# ArbPwrBoost_P2.net
KiCad netlist of a schematic drawn in Altium Designer
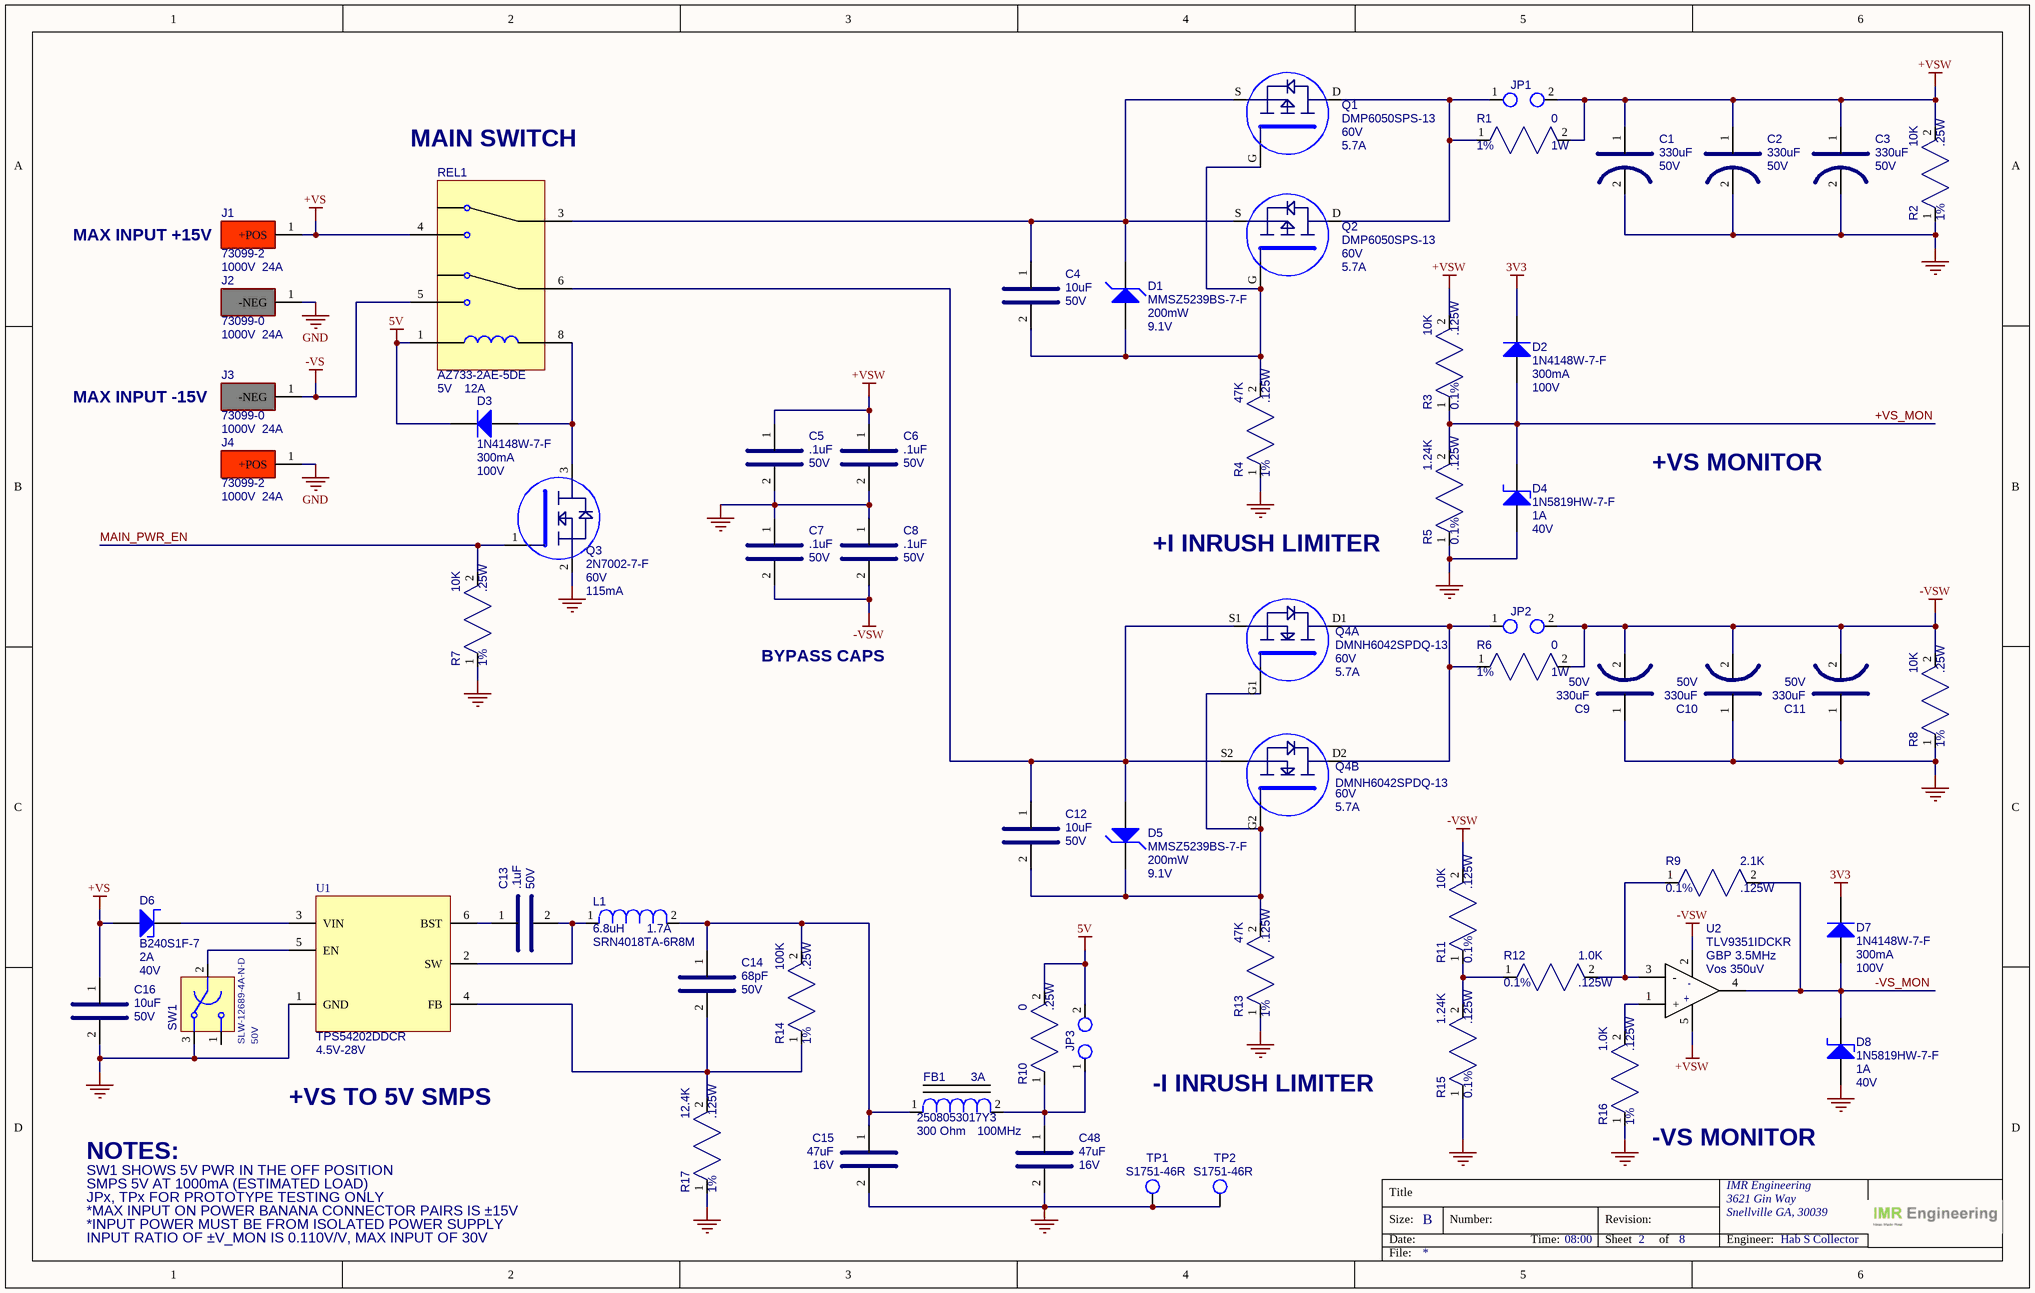
[diagram p0: ArbPwrBoost_P2.SchDoc]

(export (version "E")
  (design (tool "Eeschema 10.0.6"))
  (components
    (comp (ref "C1")
      (value "330uF")
      (footprint "PANASONIC_EEEFK0J332AQ")
      (description "CAP ALE 330UF 20% 50V SMD")
      (fields
        (field (name "MFG") "EEV-FK1H331Q")
        (field (name "VOLTAGE") "50V")
        (field (name "Comment") "Panasonic Electronic")
      )
      (libsource (lib "IMR_LIB_SCH_R2") (part "CAP_330UF_50V_ALE"))
    )
    (comp (ref "C2")
      (value "330uF")
      (footprint "PANASONIC_EEEFK0J332AQ")
      (description "CAP ALE 330UF 20% 50V SMD")
      (fields
        (field (name "MFG") "EEV-FK1H331Q")
        (field (name "VOLTAGE") "50V")
        (field (name "Comment") "Panasonic Electronic")
      )
      (libsource (lib "IMR_LIB_SCH_R2") (part "CAP_330UF_50V_ALE"))
    )
    (comp (ref "C3")
      (value "330uF")
      (footprint "PANASONIC_EEEFK0J332AQ")
      (description "CAP ALE 330UF 20% 50V SMD")
      (fields
        (field (name "MFG") "EEV-FK1H331Q")
        (field (name "VOLTAGE") "50V")
        (field (name "Comment") "Panasonic Electronic")
      )
      (libsource (lib "IMR_LIB_SCH_R2") (part "CAP_330UF_50V_ALE"))
    )
    (comp (ref "C4")
      (value "10uF")
      (footprint "CAP_0805")
      (description "CAP CER 10UF 50V X5R 0805")
      (fields
        (field (name "MFG") "Murata Electronics")
        (field (name "VOLTAGE") "50V")
        (field (name "Comment") "GRM21BR61H106KE43L")
      )
      (libsource (lib "IMR_LIB_SCH_R2") (part "CAP_SMD_10UF_50V_0805"))
    )
    (comp (ref "C5")
      (value ".1uF")
      (footprint "CAP_0805")
      (description "CAP CER 0.1UF 50V X7R 0805")
      (fields
        (field (name "MFG") "KYOCERA AVX")
        (field (name "VOLTAGE") "50V")
        (field (name "Comment") "KGM21NR71H104KT")
      )
      (libsource (lib "IMR_LIB_SCH_R2") (part "CAP_SMD_0.1UF_50V_0805"))
    )
    (comp (ref "C6")
      (value ".1uF")
      (footprint "CAP_0805")
      (description "CAP CER 0.1UF 50V X7R 0805")
      (fields
        (field (name "MFG") "KYOCERA AVX")
        (field (name "VOLTAGE") "50V")
        (field (name "Comment") "KGM21NR71H104KT")
      )
      (libsource (lib "IMR_LIB_SCH_R2") (part "CAP_SMD_0.1UF_50V_0805"))
    )
    (comp (ref "C7")
      (value ".1uF")
      (footprint "CAP_0805")
      (description "CAP CER 0.1UF 50V X7R 0805")
      (fields
        (field (name "MFG") "KYOCERA AVX")
        (field (name "VOLTAGE") "50V")
        (field (name "Comment") "KGM21NR71H104KT")
      )
      (libsource (lib "IMR_LIB_SCH_R2") (part "CAP_SMD_0.1UF_50V_0805"))
    )
    (comp (ref "C8")
      (value ".1uF")
      (footprint "CAP_0805")
      (description "CAP CER 0.1UF 50V X7R 0805")
      (fields
        (field (name "MFG") "KYOCERA AVX")
        (field (name "VOLTAGE") "50V")
        (field (name "Comment") "KGM21NR71H104KT")
      )
      (libsource (lib "IMR_LIB_SCH_R2") (part "CAP_SMD_0.1UF_50V_0805"))
    )
    (comp (ref "C9")
      (value "330uF")
      (footprint "PANASONIC_EEEFK0J332AQ")
      (description "CAP ALE 330UF 20% 50V SMD")
      (fields
        (field (name "MFG") "EEV-FK1H331Q")
        (field (name "VOLTAGE") "50V")
        (field (name "Comment") "Panasonic Electronic")
      )
      (libsource (lib "IMR_LIB_SCH_R2") (part "CAP_330UF_50V_ALE"))
    )
    (comp (ref "C10")
      (value "330uF")
      (footprint "PANASONIC_EEEFK0J332AQ")
      (description "CAP ALE 330UF 20% 50V SMD")
      (fields
        (field (name "MFG") "EEV-FK1H331Q")
        (field (name "VOLTAGE") "50V")
        (field (name "Comment") "Panasonic Electronic")
      )
      (libsource (lib "IMR_LIB_SCH_R2") (part "CAP_330UF_50V_ALE"))
    )
    (comp (ref "C11")
      (value "330uF")
      (footprint "PANASONIC_EEEFK0J332AQ")
      (description "CAP ALE 330UF 20% 50V SMD")
      (fields
        (field (name "MFG") "EEV-FK1H331Q")
        (field (name "VOLTAGE") "50V")
        (field (name "Comment") "Panasonic Electronic")
      )
      (libsource (lib "IMR_LIB_SCH_R2") (part "CAP_330UF_50V_ALE"))
    )
    (comp (ref "C12")
      (value "10uF")
      (footprint "CAP_0805")
      (description "CAP CER 10UF 50V X5R 0805")
      (fields
        (field (name "MFG") "Murata Electronics")
        (field (name "VOLTAGE") "50V")
        (field (name "Comment") "GRM21BR61H106KE43L")
      )
      (libsource (lib "IMR_LIB_SCH_R2") (part "CAP_SMD_10UF_50V_0805"))
    )
    (comp (ref "C13")
      (value ".1uF")
      (footprint "CAP_0805")
      (description "CAP CER 0.1UF 50V X7R 0805")
      (fields
        (field (name "MFG") "KYOCERA AVX")
        (field (name "VOLTAGE") "50V")
        (field (name "Comment") "KGM21NR71H104KT")
      )
      (libsource (lib "IMR_LIB_SCH_R2") (part "CAP_SMD_0.1UF_50V_0805"))
    )
    (comp (ref "C14")
      (value "68pF")
      (footprint "CAP_0805")
      (description "CAP CER 68PF 50V X7R 0805")
      (fields
        (field (name "MFG") "KEMET")
        (field (name "VOLTAGE") "50V")
        (field (name "Comment") "C0805C680K5RACAUTO")
      )
      (libsource (lib "IMR_LIB_SCH_R2") (part "CAP_SMD_68PF_50V_0805"))
    )
    (comp (ref "C15")
      (value "47uF")
      (footprint "CAP_1210")
      (description "CAP CER 47UF 50V X5R 1210")
      (fields
        (field (name "MFG") "Murata Electronics")
        (field (name "VOLTAGE") "16V")
        (field (name "Comment") "GRM32ER60J476ME20L")
      )
      (libsource (lib "IMR_LIB_SCH_R2") (part "CAP_SMD_47UF_16V_1210"))
    )
    (comp (ref "C16")
      (value "10uF")
      (footprint "CAP_0805")
      (description "CAP CER 10UF 50V X5R 0805")
      (fields
        (field (name "MFG") "Murata Electronics")
        (field (name "VOLTAGE") "50V")
        (field (name "Comment") "GRM21BR61H106KE43L")
      )
      (libsource (lib "IMR_LIB_SCH_R2") (part "CAP_SMD_10UF_50V_0805"))
    )
    (comp (ref "C48")
      (value "47uF")
      (footprint "CAP_1210")
      (description "CAP CER 47UF 50V X5R 1210")
      (fields
        (field (name "MFG") "Murata Electronics")
        (field (name "VOLTAGE") "16V")
        (field (name "Comment") "GRM32ER60J476ME20L")
      )
      (libsource (lib "IMR_LIB_SCH_R2") (part "CAP_SMD_47UF_16V_1210"))
    )
    (comp (ref "D1")
      (value "9.1V")
      (footprint "SOD323")
      (description "DIODE ZENER 9.1V 200MW SOD323")
      (fields
        (field (name "MFG") "Diodes Inc")
        (field (name "MFG_PN") "MMSZ5239BS-7-F")
        (field (name "POWER") "200mW")
        (field (name "Comment") "MMSZ5239BS-7-F")
      )
      (libsource (lib "IMR_LIB_SCH_R2") (part "DIODE_ZENER_MMSZ5239BS-7-F"))
    )
    (comp (ref "D2")
      (value "100V")
      (footprint "SOD123")
      (description "RELAY REED SPDT 250MA 5V")
      (fields
        (field (name "MFG") "Diodes Inc")
        (field (name "MFG_PN") "1N4148W-7-F")
        (field (name "CURRENT") "300mA")
        (field (name "Comment") "1N4148W-7-F")
      )
      (libsource (lib "IMR_LIB_SCH_R2") (part "DIODE_1N4148W-7-F"))
    )
    (comp (ref "D3")
      (value "100V")
      (footprint "SOD123")
      (description "RELAY REED SPDT 250MA 5V")
      (fields
        (field (name "MFG") "Diodes Inc")
        (field (name "MFG_PN") "1N4148W-7-F")
        (field (name "CURRENT") "300mA")
        (field (name "Comment") "1N4148W-7-F")
      )
      (libsource (lib "IMR_LIB_SCH_R2") (part "DIODE_1N4148W-7-F"))
    )
    (comp (ref "D4")
      (value "40V")
      (footprint "SOD123")
      (description "DIODE SCHOTTKY 40V 1A SOD123")
      (fields
        (field (name "MFG") "Diodes Inc")
        (field (name "MFG_PN") "1N5819HW-7-F")
        (field (name "CURRENT") "1A")
        (field (name "Comment") "1N5819HW-7-F")
      )
      (libsource (lib "IMR_LIB_SCH_R2") (part "DIODE_SCHOTTKY_1N5819HW-7-F"))
    )
    (comp (ref "D5")
      (value "9.1V")
      (footprint "SOD323")
      (description "DIODE ZENER 9.1V 200MW SOD323")
      (fields
        (field (name "MFG") "Diodes Inc")
        (field (name "MFG_PN") "MMSZ5239BS-7-F")
        (field (name "POWER") "200mW")
        (field (name "Comment") "MMSZ5239BS-7-F")
      )
      (libsource (lib "IMR_LIB_SCH_R2") (part "DIODE_ZENER_MMSZ5239BS-7-F"))
    )
    (comp (ref "D6")
      (value "40V")
      (footprint "SOD123F")
      (description "DIODE SCHOTTKY 40V 2A SOD123F")
      (fields
        (field (name "MFG") "Diodes Inc")
        (field (name "MFG_PN") "B240S1F-7")
        (field (name "CURRENT") "2A")
        (field (name "Comment") "B240S1F-7")
      )
      (libsource (lib "IMR_LIB_SCH_R2") (part "DIODE_SCHOTTKY_B240S1F-7"))
    )
    (comp (ref "D7")
      (value "100V")
      (footprint "SOD123")
      (description "RELAY REED SPDT 250MA 5V")
      (fields
        (field (name "MFG") "Diodes Inc")
        (field (name "MFG_PN") "1N4148W-7-F")
        (field (name "CURRENT") "300mA")
        (field (name "Comment") "1N4148W-7-F")
      )
      (libsource (lib "IMR_LIB_SCH_R2") (part "DIODE_1N4148W-7-F"))
    )
    (comp (ref "D8")
      (value "40V")
      (footprint "SOD123")
      (description "DIODE SCHOTTKY 40V 1A SOD123")
      (fields
        (field (name "MFG") "Diodes Inc")
        (field (name "MFG_PN") "1N5819HW-7-F")
        (field (name "CURRENT") "1A")
        (field (name "Comment") "1N5819HW-7-F")
      )
      (libsource (lib "IMR_LIB_SCH_R2") (part "DIODE_SCHOTTKY_1N5819HW-7-F"))
    )
    (comp (ref "FB1")
      (value "300 Ohm")
      (footprint "FERRITE_0805")
      (description "FERRITE BEAD 300 OHM 0805 1LN")
      (fields
        (field (name "MFG") "Fair-Rite")
        (field (name "FREQUENCY") "100MHz")
        (field (name "MFG_PN") "2508053017Y3")
        (field (name "CURRENT") "3A")
        (field (name "Comment") "2508053017Y3")
      )
      (libsource (lib "IMR_LIB_SCH_R2") (part "FERRITE_2508053017Y3"))
    )
    (comp (ref "J1")
      (value "1000V")
      (footprint "Pomona_73099-2")
      (description "CONN 4mm Banana Socket Right Angle PCB RED")
      (fields
        (field (name "MFG") "Pomona")
        (field (name "MFG_PN") "73099-2")
        (field (name "CURRENT") "24A")
        (field (name "Comment") "73099-2")
      )
      (libsource (lib "IMR_LIB_SCH_R2") (part "CONN_PANOMA_73099-2"))
    )
    (comp (ref "J2")
      (value "1000V")
      (footprint "Pomona_73099-0")
      (description "CONN 4mm Banana Socket Right Angle PCB BLK")
      (fields
        (field (name "MFG") "Pomona")
        (field (name "MFG_PN") "73099-0")
        (field (name "CURRENT") "24A")
        (field (name "Comment") "73099-0")
      )
      (libsource (lib "IMR_LIB_SCH_R2") (part "CONN_PANOMA_73099-0"))
    )
    (comp (ref "J3")
      (value "1000V")
      (footprint "Pomona_73099-0")
      (description "CONN 4mm Banana Socket Right Angle PCB BLK")
      (fields
        (field (name "MFG") "Pomona")
        (field (name "MFG_PN") "73099-0")
        (field (name "CURRENT") "24A")
        (field (name "Comment") "73099-0")
      )
      (libsource (lib "IMR_LIB_SCH_R2") (part "CONN_PANOMA_73099-0"))
    )
    (comp (ref "J4")
      (value "1000V")
      (footprint "Pomona_73099-2")
      (description "CONN 4mm Banana Socket Right Angle PCB RED")
      (fields
        (field (name "MFG") "Pomona")
        (field (name "MFG_PN") "73099-2")
        (field (name "CURRENT") "24A")
        (field (name "Comment") "73099-2")
      )
      (libsource (lib "IMR_LIB_SCH_R2") (part "CONN_PANOMA_73099-2"))
    )
    (comp (ref "JP1")
      (value "PREC002SFAN-RC")
      (footprint "HDR_1X2_100MILL")
      (description "CONN HEADER VERT 2POS 2.54MM")
      (fields (field (name "MFG") "Sullins Connector Solutions"))
      (libsource (lib "IMR_LIB_SCH_R2") (part "CONN_JUMPER_2P_100MIL_VERT"))
    )
    (comp (ref "JP2")
      (value "PREC002SFAN-RC")
      (footprint "HDR_1X2_100MILL")
      (description "CONN HEADER VERT 2POS 2.54MM")
      (fields (field (name "MFG") "Sullins Connector Solutions"))
      (libsource (lib "IMR_LIB_SCH_R2") (part "CONN_JUMPER_2P_100MIL_VERT"))
    )
    (comp (ref "JP3")
      (value "PREC002SFAN-RC")
      (footprint "HDR_1X2_100MILL")
      (description "CONN HEADER VERT 2POS 2.54MM")
      (fields (field (name "MFG") "Sullins Connector Solutions"))
      (libsource (lib "IMR_LIB_SCH_R2") (part "CONN_JUMPER_2P_100MIL_VERT"))
    )
    (comp (ref "L1")
      (value "6.8uH")
      (footprint "SRN4018TA")
      (description "FIXED IND 6.8UH 1.7A 98 MOHM SMD")
      (fields
        (field (name "MFG") "Bourns Inc.")
        (field (name "TOLERANCE") "20%")
        (field (name "MFG_PN") "SRN4018TA-6R8M")
        (field (name "CURRENT") "1.7A")
      )
      (libsource (lib "IMR_LIB_SCH_R2") (part "INDUCTOR_SRN4018TA-6R8M"))
    )
    (comp (ref "Q1")
      (value "60V")
      (footprint "DMP3007SPS13")
      (description "MOSFET P-CH 60V 5.7A PWRDI5060-8")
      (fields
        (field (name "MFG") "Diodes Inc")
        (field (name "MFG_PN") "DMP6050SPS-13")
        (field (name "CURRENT") "5.7A")
        (field (name "Comment") "DMP6050SPS-13")
      )
      (libsource (lib "IMR_LIB_SCH_R2") (part "MOSFET_PCH_DMP6050SPS-13"))
    )
    (comp (ref "Q2")
      (value "60V")
      (footprint "DMP3007SPS13")
      (description "MOSFET P-CH 60V 5.7A PWRDI5060-8")
      (fields
        (field (name "MFG") "Diodes Inc")
        (field (name "MFG_PN") "DMP6050SPS-13")
        (field (name "CURRENT") "5.7A")
        (field (name "Comment") "DMP6050SPS-13")
      )
      (libsource (lib "IMR_LIB_SCH_R2") (part "MOSFET_PCH_DMP6050SPS-13"))
    )
    (comp (ref "Q3")
      (value "60V")
      (footprint "SOT-23")
      (description "MOSFET N-CH 60V 115MA SOT23-3")
      (fields
        (field (name "MFG") "Diodes Inc")
        (field (name "MFG_PN") "2N7002-7-F")
        (field (name "CURRENT") "115mA")
        (field (name "Comment") "2N7002-7-F")
      )
      (libsource (lib "IMR_LIB_SCH_R2") (part "MOSFET_NCH_2N7002-7-F"))
    )
    (comp (ref "Q4")
      (value "60V")
      (footprint "TRANS_DMP2002UPS-13")
      (description "MOSFET NCH 60V 5.7A POWERDI")
      (fields
        (field (name "MFG") "Diodes Inc")
        (field (name "MFG_PN") "DMNH6042SPDQ-13")
        (field (name "CURRENT") "5.7A")
        (field (name "Comment") "DMNH6042SPDQ-13")
      )
      (libsource (lib "IMR_LIB_SCH_R2") (part "MOSFET_NCH_DMNH6042SPDQ-13"))
    )
    (comp (ref "R1")
      (value "0")
      (footprint "RES_2512")
      (description "RES SMD 0 OHM 1% 1W 2512")
      (fields
        (field (name "MFG") "Yageo")
        (field (name "TOLERANCE") "1%")
        (field (name "POWER") "1W")
        (field (name "Comment") "RC2512JK-070RL")
      )
      (libsource (lib "IMR_LIB_SCH_R2") (part "RES_SMD_0_2512_1W_1%"))
    )
    (comp (ref "R2")
      (value "10K")
      (footprint "RES_0805")
      (description "RES SMD 10K OHM 1% 1/4W 0805")
      (fields
        (field (name "MFG") "Yageo")
        (field (name "POWER") ".25W")
        (field (name "TOLERANCE") "1%")
        (field (name "Comment") "RC0805FR-7W10KL")
      )
      (libsource (lib "IMR_LIB_SCH_R2") (part "RES_SMD_10K_0805_1/4W_1%"))
    )
    (comp (ref "R3")
      (value "10K")
      (footprint "RES_0805")
      (description "RES SMD 10K OHM 0.1% 1/8W 0805")
      (fields
        (field (name "MFG") "Yageo")
        (field (name "POWER") ".125W")
        (field (name "TOLERANCE") "0.1%")
        (field (name "Comment") "RP0805BRD0710KL")
      )
      (libsource (lib "IMR_LIB_SCH_R2") (part "RES_SMD_10K_0805_1/8W_0.1%"))
    )
    (comp (ref "R4")
      (value "47K")
      (footprint "RES_0805")
      (description "RES SMD 47K OHM 1% 1/8W 0805")
      (fields
        (field (name "MFG") "Yageo")
        (field (name "POWER") ".125W")
        (field (name "TOLERANCE") "1%")
        (field (name "Comment") "RC0805FR-1347KL")
      )
      (libsource (lib "IMR_LIB_SCH_R2") (part "RES_SMD_47K_0805_1/8W_1%"))
    )
    (comp (ref "R5")
      (value "1.24K")
      (footprint "RES_0805")
      (description "RES SMD 1.24K OHM 0.1% 1/8W 0805")
      (fields
        (field (name "MFG") "Yageo")
        (field (name "POWER") ".125W")
        (field (name "TOLERANCE") "0.1%")
        (field (name "Comment") "RT0805BRD071K24L")
      )
      (libsource (lib "IMR_LIB_SCH_R2") (part "RES_SMD_1.24K_0805_1/8W_0.1%"))
    )
    (comp (ref "R6")
      (value "0")
      (footprint "RES_2512")
      (description "RES SMD 0 OHM 1% 1W 2512")
      (fields
        (field (name "MFG") "Yageo")
        (field (name "TOLERANCE") "1%")
        (field (name "POWER") "1W")
        (field (name "Comment") "RC2512JK-070RL")
      )
      (libsource (lib "IMR_LIB_SCH_R2") (part "RES_SMD_0_2512_1W_1%"))
    )
    (comp (ref "R7")
      (value "10K")
      (footprint "RES_0805")
      (description "RES SMD 10K OHM 1% 1/4W 0805")
      (fields
        (field (name "MFG") "Yageo")
        (field (name "POWER") ".25W")
        (field (name "TOLERANCE") "1%")
        (field (name "Comment") "RC0805FR-7W10KL")
      )
      (libsource (lib "IMR_LIB_SCH_R2") (part "RES_SMD_10K_0805_1/4W_1%"))
    )
    (comp (ref "R8")
      (value "10K")
      (footprint "RES_0805")
      (description "RES SMD 10K OHM 1% 1/4W 0805")
      (fields
        (field (name "MFG") "Yageo")
        (field (name "POWER") ".25W")
        (field (name "TOLERANCE") "1%")
        (field (name "Comment") "RC0805FR-7W10KL")
      )
      (libsource (lib "IMR_LIB_SCH_R2") (part "RES_SMD_10K_0805_1/4W_1%"))
    )
    (comp (ref "R9")
      (value "2.1K")
      (footprint "RES_0805")
      (description "RES SMD 2.1K OHM 0.1% 1/8W 0805")
      (fields
        (field (name "MFG") "Yageo")
        (field (name "POWER") ".125W")
        (field (name "TOLERANCE") "0.1%")
        (field (name "Comment") "RT0805BRD072K1L")
      )
      (libsource (lib "IMR_LIB_SCH_R2") (part "RES_SMD_2.1K_0805_1/8W_0.1%"))
    )
    (comp (ref "R10")
      (value "0")
      (footprint "RES_0805")
      (description "RES SMD 0 OHM 1% 1/8W 0805")
      (fields (field (name "MFG") "Yageo") (field (name "TOLERANCE") "1%") (field (name "POWER") ".25W"))
      (libsource (lib "IMR_LIB_SCH_R2") (part "RES_SMD_0_0805_1/8W_1%"))
    )
    (comp (ref "R11")
      (value "10K")
      (footprint "RES_0805")
      (description "RES SMD 10K OHM 0.1% 1/8W 0805")
      (fields
        (field (name "MFG") "Yageo")
        (field (name "POWER") ".125W")
        (field (name "TOLERANCE") "0.1%")
        (field (name "Comment") "RP0805BRD0710KL")
      )
      (libsource (lib "IMR_LIB_SCH_R2") (part "RES_SMD_10K_0805_1/8W_0.1%"))
    )
    (comp (ref "R12")
      (value "1.0K")
      (footprint "RES_0805")
      (description "RES SMD 1.0K OHM 0.1% 1/8W 0805")
      (fields
        (field (name "MFG") "Yageo")
        (field (name "POWER") ".125W")
        (field (name "TOLERANCE") "0.1%")
        (field (name "Comment") "RT0805BRD071KL")
      )
      (libsource (lib "IMR_LIB_SCH_R2") (part "RES_SMD_1.0K_0805_1/8W_0.1%"))
    )
    (comp (ref "R13")
      (value "47K")
      (footprint "RES_0805")
      (description "RES SMD 47K OHM 1% 1/8W 0805")
      (fields
        (field (name "MFG") "Yageo")
        (field (name "POWER") ".125W")
        (field (name "TOLERANCE") "1%")
        (field (name "Comment") "RC0805FR-1347KL")
      )
      (libsource (lib "IMR_LIB_SCH_R2") (part "RES_SMD_47K_0805_1/8W_1%"))
    )
    (comp (ref "R14")
      (value "100K")
      (footprint "RES_0805")
      (description "RES SMD 100K OHM 1% 1/4W 0805")
      (fields
        (field (name "MFG") "Yageo")
        (field (name "POWER") ".25W")
        (field (name "TOLERANCE") "1%")
        (field (name "Comment") "RC0805FR-07100KL")
      )
      (libsource (lib "IMR_LIB_SCH_R2") (part "RES_SMD_100K_0805_1/4W_1%"))
    )
    (comp (ref "R15")
      (value "1.24K")
      (footprint "RES_0805")
      (description "RES SMD 1.24K OHM 0.1% 1/8W 0805")
      (fields
        (field (name "MFG") "Yageo")
        (field (name "POWER") ".125W")
        (field (name "TOLERANCE") "0.1%")
        (field (name "Comment") "RT0805BRD071K24L")
      )
      (libsource (lib "IMR_LIB_SCH_R2") (part "RES_SMD_1.24K_0805_1/8W_0.1%"))
    )
    (comp (ref "R16")
      (value "1.0K")
      (footprint "RES_0805")
      (description "RES SMD 1.0K OHM 1% 1/8W 0805")
      (fields
        (field (name "MFG") "Yageo")
        (field (name "POWER") ".125W")
        (field (name "TOLERANCE") "1%")
        (field (name "Comment") "RC0805FR-071KL")
      )
      (libsource (lib "IMR_LIB_SCH_R2") (part "RES_SMD_1.0K_0805_1/8W_1%"))
    )
    (comp (ref "R17")
      (value "12.4K")
      (footprint "RES_0805")
      (description "RES SMD 12.4K OHM 1% 1/8W 0805")
      (fields
        (field (name "MFG") "Yageo")
        (field (name "POWER") ".125W")
        (field (name "TOLERANCE") "1%")
        (field (name "Comment") "RC0805FR-0712K4L")
      )
      (libsource (lib "IMR_LIB_SCH_R2") (part "RES_SMD_12.4K_0805_1/8W_1%"))
    )
    (comp (ref "REL1")
      (value "5V")
      (footprint "AZ733")
      (description "RELAY REED SPDT 250MA 5V")
      (fields
        (field (name "MFG") "American Zettler")
        (field (name "MFG_PN") "AZ733-2AE-5DE")
        (field (name "CURRENT") "12A")
        (field (name "Comment") "AZ733-2AE-5DE")
      )
      (libsource (lib "IMR_LIB_SCH_R2") (part "RELAY_AZ733-2AE-5DE"))
    )
    (comp (ref "SW1")
      (value "50V")
      (footprint "SLW126894AND")
      (description "SWITCH SLIDE SPDT 300MA 50V")
      (fields
        (field (name "MFG") "Same Sky")
        (field (name "MFG_PN") "SLW-12689-4A-N-D")
        (field (name "Comment") "SLW-12689-4A-N-D")
      )
      (libsource (lib "IMR_LIB_SCH_R2") (part "SWITCH_SLW-12689-4A-N-D"))
    )
    (comp (ref "TP1")
      (value "S1751-46R")
      (footprint "HARWIN_S1751")
      (description "PCB TEST POINT CONNECT")
      (fields (field (name "MFG") "Harwin Inc") (field (name "MFG_PN") "S1751-46R"))
      (libsource (lib "IMR_LIB_SCH_R2") (part "CONN_TEST_POINT_S1751-46R"))
    )
    (comp (ref "TP2")
      (value "S1751-46R")
      (footprint "HARWIN_S1751")
      (description "PCB TEST POINT CONNECT")
      (fields (field (name "MFG") "Harwin Inc") (field (name "MFG_PN") "S1751-46R"))
      (libsource (lib "IMR_LIB_SCH_R2") (part "CONN_TEST_POINT_S1751-46R"))
    )
    (comp (ref "U1")
      (value "4.5V-28V")
      (footprint "SOT-23-6")
      (description "IC REG BUCK ADJ 2A SOT23")
      (fields
        (field (name "MFG") "Texas Instruments")
        (field (name "MFG_PN") "TPS54202DDCR")
        (field (name "Comment") "TPS54202DDCR")
      )
      (libsource (lib "IMR_LIB_SCH") (part "IC_TPS54202DDCR"))
    )
    (comp (ref "U2")
      (value "GBP 3.5MHz")
      (footprint "SOT-353")
      (description "IC OPAMP GP 3.5MHZ 350uV C70-5")
      (fields
        (field (name "MFG") "Texas Instruments")
        (field (name "MFG_PN") "TLV9351IDCKR")
        (field (name "VOS") "Vos 350uV")
        (field (name "Comment") "TLV9351IDCKR")
      )
      (libsource (lib "IMR_LIB_SCH_R2") (part "OPAMP_TLV9351IDCKR"))
    )
  )
  (nets
    (net (code "1") (name "+VS") (class "Default")
      (node (ref "C16") (pin "1") (pinfunction "1_1") (pintype "passive"))
      (node (ref "D6") (pin "1") (pinfunction "A_1") (pintype "passive"))
      (node (ref "J1") (pin "1") (pinfunction "+POS_1") (pintype "passive"))
      (node (ref "REL1") (pin "4") (pintype "passive"))
    )
    (net (code "2") (name "+VSW") (class "Default")
      (node (ref "C1") (pin "1") (pinfunction "1_1") (pintype "passive"))
      (node (ref "C2") (pin "1") (pinfunction "1_1") (pintype "passive"))
      (node (ref "C3") (pin "1") (pinfunction "1_1") (pintype "passive"))
      (node (ref "C5") (pin "1") (pinfunction "1_1") (pintype "passive"))
      (node (ref "C6") (pin "1") (pinfunction "1_1") (pintype "passive"))
      (node (ref "JP1") (pin "2") (pintype "passive"))
      (node (ref "R1") (pin "2") (pinfunction "2_2") (pintype "passive"))
      (node (ref "R2") (pin "2") (pinfunction "2_2") (pintype "passive"))
      (node (ref "R3") (pin "2") (pinfunction "2_2") (pintype "passive"))
      (node (ref "U2") (pin "5") (pintype "passive"))
    )
    (net (code "3") (name "-VS") (class "Default")
      (node (ref "J3") (pin "1") (pinfunction "-NEG_1") (pintype "passive"))
      (node (ref "REL1") (pin "5") (pintype "passive"))
    )
    (net (code "4") (name "-VSW") (class "Default")
      (node (ref "C10") (pin "2") (pinfunction "2_2") (pintype "passive"))
      (node (ref "C11") (pin "2") (pinfunction "2_2") (pintype "passive"))
      (node (ref "C7") (pin "2") (pinfunction "2_2") (pintype "passive"))
      (node (ref "C8") (pin "2") (pinfunction "2_2") (pintype "passive"))
      (node (ref "C9") (pin "2") (pinfunction "2_2") (pintype "passive"))
      (node (ref "JP2") (pin "2") (pintype "passive"))
      (node (ref "R11") (pin "2") (pinfunction "2_2") (pintype "passive"))
      (node (ref "R6") (pin "2") (pinfunction "2_2") (pintype "passive"))
      (node (ref "R8") (pin "2") (pinfunction "2_2") (pintype "passive"))
      (node (ref "U2") (pin "2") (pintype "passive"))
    )
    (net (code "5") (name "/+VS_MON") (class "Default")
      (node (ref "D2") (pin "1") (pinfunction "A_1") (pintype "passive"))
      (node (ref "D4") (pin "2") (pinfunction "K_2") (pintype "passive"))
      (node (ref "R3") (pin "1") (pinfunction "1_1") (pintype "passive"))
      (node (ref "R5") (pin "2") (pinfunction "2_2") (pintype "passive"))
    )
    (net (code "6") (name "/-VS_MON") (class "Default")
      (node (ref "D7") (pin "1") (pinfunction "A_1") (pintype "passive"))
      (node (ref "D8") (pin "2") (pinfunction "K_2") (pintype "passive"))
      (node (ref "R9") (pin "2") (pinfunction "2_2") (pintype "passive"))
      (node (ref "U2") (pin "4") (pintype "passive"))
    )
    (net (code "7") (name "/MAIN_PWR_EN") (class "Default")
      (node (ref "Q3") (pin "1") (pinfunction "B_1") (pintype "passive"))
      (node (ref "R7") (pin "2") (pinfunction "2_2") (pintype "passive"))
    )
    (net (code "8") (name "3V3") (class "Default")
      (node (ref "D2") (pin "2") (pinfunction "K_2") (pintype "passive"))
      (node (ref "D7") (pin "2") (pinfunction "K_2") (pintype "passive"))
    )
    (net (code "9") (name "5V") (class "Default")
      (node (ref "D3") (pin "2") (pinfunction "K_2") (pintype "passive"))
      (node (ref "JP3") (pin "2") (pintype "passive"))
      (node (ref "R10") (pin "2") (pinfunction "2_2") (pintype "passive"))
      (node (ref "REL1") (pin "1") (pintype "passive"))
    )
    (net (code "10") (name "GND") (class "Default")
      (node (ref "C1") (pin "2") (pinfunction "2_2") (pintype "passive"))
      (node (ref "C10") (pin "1") (pinfunction "1_1") (pintype "passive"))
      (node (ref "C11") (pin "1") (pinfunction "1_1") (pintype "passive"))
      (node (ref "C15") (pin "2") (pinfunction "2_2") (pintype "passive"))
      (node (ref "C16") (pin "2") (pinfunction "2_2") (pintype "passive"))
      (node (ref "C2") (pin "2") (pinfunction "2_2") (pintype "passive"))
      (node (ref "C3") (pin "2") (pinfunction "2_2") (pintype "passive"))
      (node (ref "C48") (pin "2") (pinfunction "2_2") (pintype "passive"))
      (node (ref "C5") (pin "2") (pinfunction "2_2") (pintype "passive"))
      (node (ref "C6") (pin "2") (pinfunction "2_2") (pintype "passive"))
      (node (ref "C7") (pin "1") (pinfunction "1_1") (pintype "passive"))
      (node (ref "C8") (pin "1") (pinfunction "1_1") (pintype "passive"))
      (node (ref "C9") (pin "1") (pinfunction "1_1") (pintype "passive"))
      (node (ref "D4") (pin "1") (pinfunction "A_1") (pintype "passive"))
      (node (ref "D8") (pin "1") (pinfunction "A_1") (pintype "passive"))
      (node (ref "J2") (pin "1") (pinfunction "-NEG_1") (pintype "passive"))
      (node (ref "J4") (pin "1") (pinfunction "+POS_1") (pintype "passive"))
      (node (ref "Q3") (pin "2") (pinfunction "E_2") (pintype "passive"))
      (node (ref "R13") (pin "1") (pinfunction "1_1") (pintype "passive"))
      (node (ref "R15") (pin "1") (pinfunction "1_1") (pintype "passive"))
      (node (ref "R16") (pin "1") (pinfunction "1_1") (pintype "passive"))
      (node (ref "R17") (pin "1") (pinfunction "1_1") (pintype "passive"))
      (node (ref "R2") (pin "1") (pinfunction "1_1") (pintype "passive"))
      (node (ref "R4") (pin "1") (pinfunction "1_1") (pintype "passive"))
      (node (ref "R5") (pin "1") (pinfunction "1_1") (pintype "passive"))
      (node (ref "R7") (pin "1") (pinfunction "1_1") (pintype "passive"))
      (node (ref "R8") (pin "1") (pinfunction "1_1") (pintype "passive"))
      (node (ref "SW1") (pin "3") (pintype "passive"))
      (node (ref "TP1") (pin "1") (pintype "passive"))
      (node (ref "TP2") (pin "1") (pintype "passive"))
      (node (ref "U1") (pin "1") (pinfunction "GND_1") (pintype "passive"))
    )
    (net (code "11") (name "Net-(C14-Pad1)") (class "Default")
      (node (ref "C14") (pin "1") (pinfunction "1_1") (pintype "passive"))
      (node (ref "C15") (pin "1") (pinfunction "1_1") (pintype "passive"))
      (node (ref "FB1") (pin "1") (pinfunction "1_1") (pintype "passive"))
      (node (ref "L1") (pin "2") (pinfunction "2_2") (pintype "passive"))
      (node (ref "R14") (pin "2") (pinfunction "2_2") (pintype "passive"))
    )
    (net (code "12") (name "Net-(C48-Pad1)") (class "Default")
      (node (ref "C48") (pin "1") (pinfunction "1_1") (pintype "passive"))
      (node (ref "FB1") (pin "2") (pinfunction "2_2") (pintype "passive"))
      (node (ref "JP3") (pin "1") (pintype "passive"))
      (node (ref "R10") (pin "1") (pinfunction "1_1") (pintype "passive"))
    )
    (net (code "13") (name "Net-(D1-A)") (class "Default")
      (node (ref "C4") (pin "2") (pinfunction "2_2") (pintype "passive"))
      (node (ref "D1") (pin "1") (pinfunction "A_1") (pintype "passive"))
      (node (ref "Q1") (pin "G") (pinfunction "G_G") (pintype "passive"))
      (node (ref "Q2") (pin "G") (pinfunction "G_G") (pintype "passive"))
      (node (ref "R4") (pin "2") (pinfunction "2_2") (pintype "passive"))
    )
    (net (code "14") (name "Net-(D1-K)") (class "Default")
      (node (ref "C4") (pin "1") (pinfunction "1_1") (pintype "passive"))
      (node (ref "D1") (pin "2") (pinfunction "K_2") (pintype "passive"))
      (node (ref "Q1") (pin "S") (pinfunction "S_S") (pintype "passive"))
      (node (ref "Q2") (pin "S") (pinfunction "S_S") (pintype "passive"))
      (node (ref "REL1") (pin "3") (pintype "passive"))
    )
    (net (code "15") (name "Net-(D3-A)") (class "Default")
      (node (ref "D3") (pin "1") (pinfunction "A_1") (pintype "passive"))
      (node (ref "Q3") (pin "3") (pinfunction "C_3") (pintype "passive"))
      (node (ref "REL1") (pin "8") (pintype "passive"))
    )
    (net (code "16") (name "Net-(D5-A)") (class "Default")
      (node (ref "C12") (pin "1") (pinfunction "1_1") (pintype "passive"))
      (node (ref "D5") (pin "1") (pinfunction "A_1") (pintype "passive"))
      (node (ref "Q4") (pin "S1") (pinfunction "S_S1") (pintype "passive"))
      (node (ref "Q4") (pin "S2") (pinfunction "S_S2") (pintype "passive"))
      (node (ref "REL1") (pin "6") (pintype "passive"))
    )
    (net (code "17") (name "Net-(D5-K)") (class "Default")
      (node (ref "C12") (pin "2") (pinfunction "2_2") (pintype "passive"))
      (node (ref "D5") (pin "2") (pinfunction "K_2") (pintype "passive"))
      (node (ref "Q4") (pin "G1") (pinfunction "G_G1") (pintype "passive"))
      (node (ref "Q4") (pin "G2") (pintype "passive"))
      (node (ref "R13") (pin "2") (pinfunction "2_2") (pintype "passive"))
    )
    (net (code "18") (name "Net-(D6-K)") (class "Default")
      (node (ref "D6") (pin "2") (pinfunction "K_2") (pintype "passive"))
      (node (ref "U1") (pin "3") (pinfunction "VIN_3") (pintype "passive"))
    )
    (net (code "19") (name "Net-(JP1-Pad1)") (class "Default")
      (node (ref "JP1") (pin "1") (pintype "passive"))
      (node (ref "Q1") (pin "D") (pinfunction "D_D") (pintype "passive"))
      (node (ref "Q2") (pin "D") (pinfunction "D_D") (pintype "passive"))
      (node (ref "R1") (pin "1") (pinfunction "1_1") (pintype "passive"))
    )
    (net (code "20") (name "Net-(Q4A-D)") (class "Default")
      (node (ref "JP2") (pin "1") (pintype "passive"))
      (node (ref "Q4") (pin "D1") (pinfunction "D_D1") (pintype "passive"))
      (node (ref "Q4") (pin "D2") (pinfunction "D_D2") (pintype "passive"))
      (node (ref "R6") (pin "1") (pinfunction "1_1") (pintype "passive"))
    )
    (net (code "21") (name "Net-(R11-Pad1)") (class "Default")
      (node (ref "R11") (pin "1") (pinfunction "1_1") (pintype "passive"))
      (node (ref "R12") (pin "1") (pinfunction "1_1") (pintype "passive"))
      (node (ref "R15") (pin "2") (pinfunction "2_2") (pintype "passive"))
    )
    (net (code "22") (name "Net-(U1-BST)") (class "Default")
      (node (ref "C13") (pin "1") (pinfunction "1_1") (pintype "passive"))
      (node (ref "U1") (pin "6") (pinfunction "BST_6") (pintype "passive"))
    )
    (net (code "23") (name "Net-(U1-EN)") (class "Default")
      (node (ref "SW1") (pin "2") (pintype "passive"))
      (node (ref "U1") (pin "5") (pinfunction "EN_5") (pintype "passive"))
    )
    (net (code "24") (name "Net-(U1-FB)") (class "Default")
      (node (ref "C14") (pin "2") (pinfunction "2_2") (pintype "passive"))
      (node (ref "R14") (pin "1") (pinfunction "1_1") (pintype "passive"))
      (node (ref "R17") (pin "2") (pinfunction "2_2") (pintype "passive"))
      (node (ref "U1") (pin "4") (pinfunction "FB_4") (pintype "passive"))
    )
    (net (code "25") (name "Net-(U1-SW)") (class "Default")
      (node (ref "C13") (pin "2") (pinfunction "2_2") (pintype "passive"))
      (node (ref "L1") (pin "1") (pinfunction "1_1") (pintype "passive"))
      (node (ref "U1") (pin "2") (pinfunction "SW_2") (pintype "passive"))
    )
    (net (code "26") (name "Net-(U2-+)") (class "Default")
      (node (ref "R16") (pin "2") (pinfunction "2_2") (pintype "passive"))
      (node (ref "U2") (pin "1") (pinfunction "+_1") (pintype "passive"))
    )
    (net (code "27") (name "Net-(U2--)") (class "Default")
      (node (ref "R12") (pin "2") (pinfunction "2_2") (pintype "passive"))
      (node (ref "R9") (pin "1") (pinfunction "1_1") (pintype "passive"))
      (node (ref "U2") (pin "3") (pinfunction "-_3") (pintype "passive"))
    )
    (net (code "28") (name "unconnected-(SW1-Pad1)") (class "Default")
      (node (ref "SW1") (pin "1") (pintype "passive"))
    )
  )
)
